# PR5009.net
KiCad netlist of a schematic drawn in EAGLE
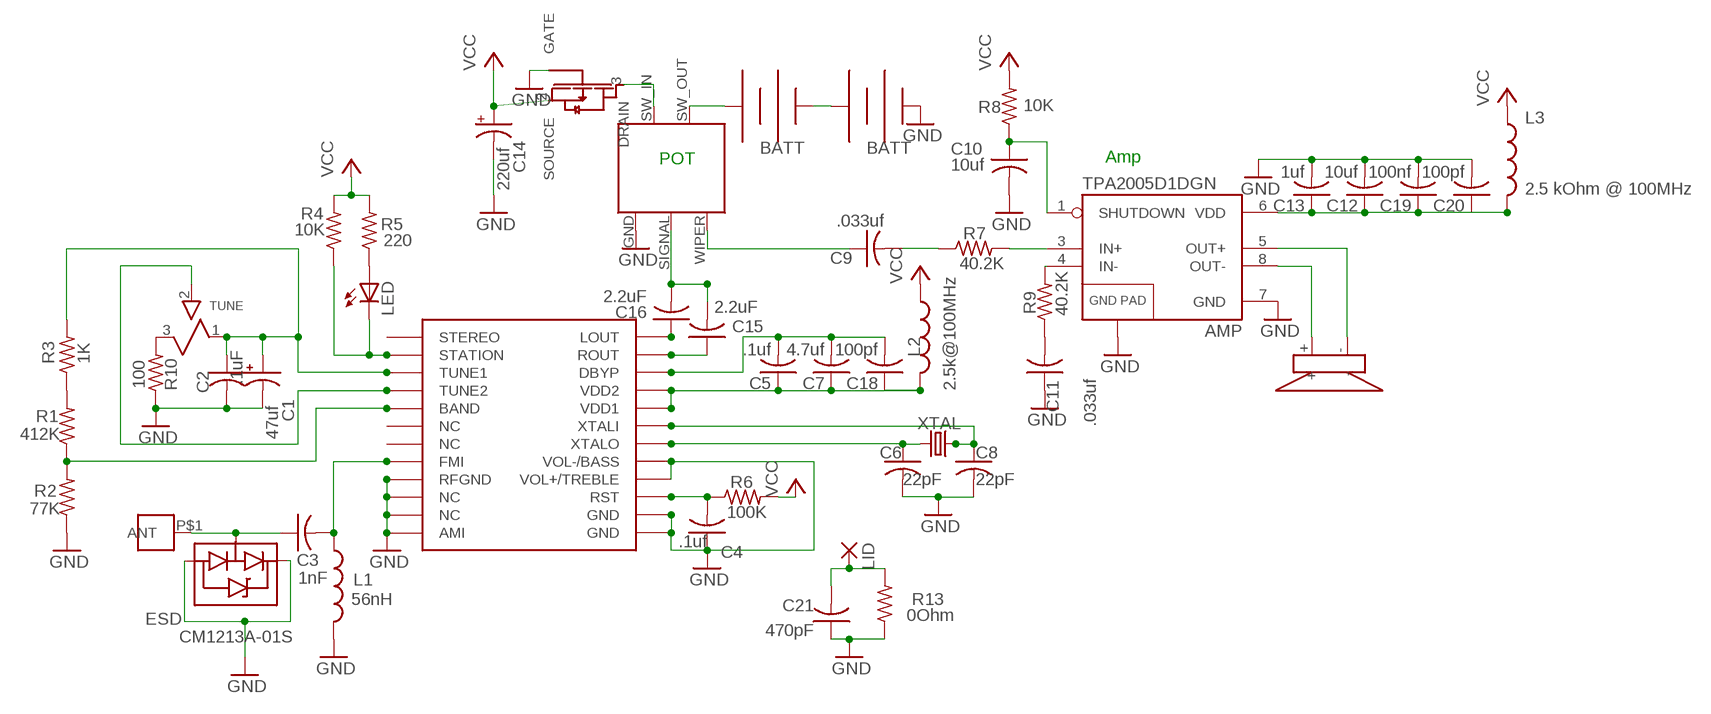
[diagram p0: schematic, sheet 1]

(export (version "E")
  (design (tool "Eeschema 10.0.6"))
  (components
    (comp (ref "AMP")
      (value "TPA2005D1DGN")
      (footprint "eagle-import:POWER-SOP8")
      (libsource (lib "eagle-import") (part "TPA2005D1DGN"))
    )
    (comp (ref "ANT")
      (value "M3_SCREW_POST")
      (footprint "eagle-import:M3_SCREW_POST")
      (libsource (lib "eagle-import") (part "M3_SCREW_POST"))
    )
    (comp (ref "C1")
      (value "47uf")
      (footprint "eagle-import:E2-5")
      (libsource (lib "eagle-import") (part "CPOL-USE2-5"))
    )
    (comp (ref "C2")
      (value ".1uF")
      (footprint "eagle-import:C0603")
      (libsource (lib "eagle-import") (part "C-USC0603"))
    )
    (comp (ref "C3")
      (value "1nF")
      (footprint "eagle-import:C0603")
      (libsource (lib "eagle-import") (part "C-USC0603"))
    )
    (comp (ref "C4")
      (value ".1uf")
      (footprint "eagle-import:C0603")
      (libsource (lib "eagle-import") (part "C-USC0603"))
    )
    (comp (ref "C5")
      (value ".1uf")
      (footprint "eagle-import:C0603")
      (libsource (lib "eagle-import") (part "C-USC0603"))
    )
    (comp (ref "C6")
      (value "22pF")
      (footprint "eagle-import:C0603")
      (libsource (lib "eagle-import") (part "C-USC0603"))
    )
    (comp (ref "C7")
      (value "4.7uf")
      (footprint "eagle-import:C0603")
      (libsource (lib "eagle-import") (part "C-USC0603"))
    )
    (comp (ref "C8")
      (value "22pF")
      (footprint "eagle-import:C0603")
      (libsource (lib "eagle-import") (part "C-USC0603"))
    )
    (comp (ref "C9")
      (value ".033uf")
      (footprint "eagle-import:C0603")
      (libsource (lib "eagle-import") (part "C-USC0603"))
    )
    (comp (ref "C10")
      (value "10uf")
      (footprint "eagle-import:C0603")
      (libsource (lib "eagle-import") (part "C-USC0603"))
    )
    (comp (ref "C11")
      (value ".033uf")
      (footprint "eagle-import:C0603")
      (libsource (lib "eagle-import") (part "C-USC0603"))
    )
    (comp (ref "C12")
      (value "10uf")
      (footprint "eagle-import:C0603")
      (libsource (lib "eagle-import") (part "C-USC0603"))
    )
    (comp (ref "C13")
      (value "1uf")
      (footprint "eagle-import:C0603")
      (libsource (lib "eagle-import") (part "C-USC0603"))
    )
    (comp (ref "C14")
      (value "220uf")
      (footprint "eagle-import:E2-5")
      (libsource (lib "eagle-import") (part "CPOL-USE2-5"))
    )
    (comp (ref "C15")
      (value "2.2uF")
      (footprint "eagle-import:C0603")
      (libsource (lib "eagle-import") (part "C-USC0603"))
    )
    (comp (ref "C16")
      (value "2.2uF")
      (footprint "eagle-import:C0603")
      (libsource (lib "eagle-import") (part "C-USC0603"))
    )
    (comp (ref "C18")
      (value "100pf")
      (footprint "eagle-import:C0603")
      (libsource (lib "eagle-import") (part "C-USC0603"))
    )
    (comp (ref "C19")
      (value "100nf")
      (footprint "eagle-import:C0603")
      (libsource (lib "eagle-import") (part "C-USC0603"))
    )
    (comp (ref "C20")
      (value "100pf")
      (footprint "eagle-import:C0603")
      (libsource (lib "eagle-import") (part "C-USC0603"))
    )
    (comp (ref "C21")
      (value "470pF")
      (footprint "eagle-import:C0603")
      (libsource (lib "eagle-import") (part "C-USC0603"))
    )
    (comp (ref "ESD")
      (value "CM1213A-01S")
      (footprint "eagle-import:SOT23-3")
      (libsource (lib "eagle-import") (part "CM1213A-01S"))
    )
    (comp (ref "FET")
      (value "SI2333DDS")
      (footprint "eagle-import:SI2333DDS")
      (libsource (lib "eagle-import") (part "SI2333DDS"))
    )
    (comp (ref "L1")
      (value "56nH")
      (footprint "eagle-import:0603")
      (libsource (lib "eagle-import") (part "INDUCTOR0603"))
    )
    (comp (ref "L2")
      (value "2.5k@100MHz")
      (footprint "eagle-import:0603")
      (libsource (lib "eagle-import") (part "INDUCTOR0603"))
    )
    (comp (ref "L3")
      (value "2.5 kOhm @ 100MHz")
      (footprint "eagle-import:0603")
      (libsource (lib "eagle-import") (part "INDUCTOR0603"))
    )
    (comp (ref "LED")
      (value "LEDCHIPLED_0805")
      (footprint "eagle-import:CHIPLED_0805")
      (libsource (lib "eagle-import") (part "LEDCHIPLED_0805"))
    )
    (comp (ref "LID")
      (value "2,54/1,0")
      (footprint "eagle-import:2,54_1,0")
      (libsource (lib "eagle-import") (part "2,54/1,0"))
    )
    (comp (ref "R1")
      (value "412K")
      (footprint "eagle-import:R0603")
      (libsource (lib "eagle-import") (part "R-US_R0603"))
    )
    (comp (ref "R2")
      (value "77K")
      (footprint "eagle-import:R0603")
      (libsource (lib "eagle-import") (part "R-US_R0603"))
    )
    (comp (ref "R3")
      (value "1K")
      (footprint "eagle-import:R0603")
      (libsource (lib "eagle-import") (part "R-US_R0603"))
    )
    (comp (ref "R4")
      (value "10K")
      (footprint "eagle-import:R0603")
      (libsource (lib "eagle-import") (part "R-US_R0603"))
    )
    (comp (ref "R5")
      (value "220")
      (footprint "eagle-import:R0603")
      (libsource (lib "eagle-import") (part "R-US_R0603"))
    )
    (comp (ref "R6")
      (value "100K")
      (footprint "eagle-import:R0603")
      (libsource (lib "eagle-import") (part "R-US_R0603"))
    )
    (comp (ref "R7")
      (value "40.2K")
      (footprint "eagle-import:R0603")
      (libsource (lib "eagle-import") (part "R-US_R0603"))
    )
    (comp (ref "R8")
      (value "10K")
      (footprint "eagle-import:R0603")
      (libsource (lib "eagle-import") (part "R-US_R0603"))
    )
    (comp (ref "R9")
      (value "40.2K")
      (footprint "eagle-import:R0603")
      (libsource (lib "eagle-import") (part "R-US_R0603"))
    )
    (comp (ref "R10")
      (value "100")
      (footprint "eagle-import:R0603")
      (libsource (lib "eagle-import") (part "R-US_R0603"))
    )
    (comp (ref "R13")
      (value "0Ohm")
      (footprint "eagle-import:R0603")
      (libsource (lib "eagle-import") (part "R-US_R0603"))
    )
    (comp (ref "TUNE")
      (value "10k")
      (footprint "eagle-import:64XR_BOURNS_TRIMPOT")
      (libsource (lib "eagle-import") (part "64XR_BOURNS_TRIMPOT"))
    )
    (comp (ref "U$1")
      (value "BK-92_MPD_AA_BATT_CLIP")
      (footprint "eagle-import:BK-92_MPD_AA_BATT_CLIP")
      (libsource (lib "eagle-import") (part "BK-92_MPD_AA_BATT_CLIP"))
    )
    (comp (ref "U$2")
      (value "BK-92_MPD_AA_BATT_CLIP")
      (footprint "eagle-import:BK-92_MPD_AA_BATT_CLIP")
      (libsource (lib "eagle-import") (part "BK-92_MPD_AA_BATT_CLIP"))
    )
    (comp (ref "U$3")
      (value "CE32A_DAYTON_SPKR")
      (footprint "eagle-import:CE32A_DAYTON_SPKR")
      (libsource (lib "eagle-import") (part "CE32A_DAYTON_SPKR"))
    )
    (comp (ref "U$4")
      (value "SI4831_FM_IC")
      (footprint "eagle-import:SI4831_FM_IC")
      (libsource (lib "eagle-import") (part "SI4831_FM_IC"))
    )
    (comp (ref "U$5")
      (value "RV170SF_TAIWANA_POT_SW")
      (footprint "eagle-import:RV170SF_TAIWANA_POT_SW")
      (libsource (lib "eagle-import") (part "RV170SF_TAIWANA_POT_SW"))
    )
    (comp (ref "XTAL")
      (value "CRYSTAL32-SMD")
      (footprint "eagle-import:CRYSTAL-32KHZ-SMD")
      (libsource (lib "eagle-import") (part "CRYSTAL32-SMD"))
    )
  )
  (nets
    (net (code "1") (name "GND") (class "Default")
      (node (ref "AMP") (pin "7") (pinfunction "GND_7") (pintype "power_in"))
      (node (ref "AMP") (pin "9") (pinfunction "GND_9") (pintype "power_in"))
      (node (ref "C1") (pin "-") (pinfunction "-_-") (pintype "passive"))
      (node (ref "C10") (pin "2") (pinfunction "2_2") (pintype "passive"))
      (node (ref "C11") (pin "1") (pinfunction "1_1") (pintype "passive"))
      (node (ref "C12") (pin "2") (pinfunction "2_2") (pintype "passive"))
      (node (ref "C13") (pin "2") (pinfunction "2_2") (pintype "passive"))
      (node (ref "C14") (pin "-") (pinfunction "-_-") (pintype "passive"))
      (node (ref "C19") (pin "2") (pinfunction "2_2") (pintype "passive"))
      (node (ref "C2") (pin "2") (pinfunction "2_2") (pintype "passive"))
      (node (ref "C20") (pin "2") (pinfunction "2_2") (pintype "passive"))
      (node (ref "C21") (pin "1") (pinfunction "1_1") (pintype "passive"))
      (node (ref "C4") (pin "1") (pinfunction "1_1") (pintype "passive"))
      (node (ref "C6") (pin "2") (pinfunction "2_2") (pintype "passive"))
      (node (ref "C8") (pin "2") (pinfunction "2_2") (pintype "passive"))
      (node (ref "ESD") (pin "2") (pinfunction "VP_2") (pintype "passive"))
      (node (ref "ESD") (pin "3") (pinfunction "VN_3") (pintype "passive"))
      (node (ref "FET") (pin "1") (pinfunction "GATE_1") (pintype "bidirectional"))
      (node (ref "L1") (pin "2") (pinfunction "2_2") (pintype "passive"))
      (node (ref "R10") (pin "1") (pinfunction "1_1") (pintype "passive"))
      (node (ref "R13") (pin "1") (pinfunction "1_1") (pintype "passive"))
      (node (ref "R2") (pin "1") (pinfunction "1_1") (pintype "passive"))
      (node (ref "U$2") (pin "NEG") (pinfunction "NEG_NEG") (pintype "bidirectional"))
      (node (ref "U$2") (pin "NEG@2") (pinfunction "NEG_NEG@2") (pintype "bidirectional"))
      (node (ref "U$4") (pin "AMI") (pinfunction "AMI_AMI") (pintype "bidirectional"))
      (node (ref "U$4") (pin "GND") (pinfunction "GND_GND") (pintype "bidirectional"))
      (node (ref "U$4") (pin "GND@2") (pinfunction "GND_GND@2") (pintype "bidirectional"))
      (node (ref "U$4") (pin "NC@3") (pinfunction "NC_NC@3") (pintype "bidirectional"))
      (node (ref "U$4") (pin "NC@4") (pinfunction "NC_NC@4") (pintype "bidirectional"))
      (node (ref "U$4") (pin "RFGND") (pinfunction "RFGND_RFGND") (pintype "bidirectional"))
      (node (ref "U$4") (pin "VOL+/TREBLE") (pinfunction "VOL+/TREBLE_VOL+/TREBLE") (pintype "bidirectional"))
      (node (ref "U$4") (pin "VOL-/BASS") (pinfunction "VOL-/BASS_VOL-/BASS") (pintype "bidirectional"))
      (node (ref "U$5") (pin "GND") (pinfunction "GND_GND") (pintype "bidirectional"))
    )
    (net (code "2") (name "Net-(AMP-IN+)") (class "Default")
      (node (ref "AMP") (pin "3") (pinfunction "IN+_3") (pintype "bidirectional"))
      (node (ref "R7") (pin "2") (pinfunction "2_2") (pintype "passive"))
    )
    (net (code "3") (name "Net-(AMP-IN-)") (class "Default")
      (node (ref "AMP") (pin "4") (pinfunction "IN-_4") (pintype "bidirectional"))
      (node (ref "R9") (pin "2") (pinfunction "2_2") (pintype "passive"))
    )
    (net (code "4") (name "Net-(AMP-OUT+)") (class "Default")
      (node (ref "AMP") (pin "5") (pinfunction "OUT+_5") (pintype "bidirectional"))
      (node (ref "U$3") (pin "-") (pinfunction "-_-") (pintype "bidirectional"))
    )
    (net (code "5") (name "Net-(AMP-OUT-)") (class "Default")
      (node (ref "AMP") (pin "8") (pinfunction "OUT-_8") (pintype "bidirectional"))
      (node (ref "U$3") (pin "+") (pinfunction "+_+") (pintype "bidirectional"))
    )
    (net (code "6") (name "Net-(AMP-SHUTDOWN)") (class "Default")
      (node (ref "AMP") (pin "1") (pinfunction "SHUTDOWN_1") (pintype "input"))
      (node (ref "C10") (pin "1") (pinfunction "1_1") (pintype "passive"))
      (node (ref "R8") (pin "1") (pinfunction "1_1") (pintype "passive"))
    )
    (net (code "7") (name "Net-(AMP-VDD)") (class "Default")
      (node (ref "AMP") (pin "6") (pinfunction "VDD_6") (pintype "power_in"))
      (node (ref "C12") (pin "1") (pinfunction "1_1") (pintype "passive"))
      (node (ref "C13") (pin "1") (pinfunction "1_1") (pintype "passive"))
      (node (ref "C19") (pin "1") (pinfunction "1_1") (pintype "passive"))
      (node (ref "C20") (pin "1") (pinfunction "1_1") (pintype "passive"))
      (node (ref "L3") (pin "2") (pinfunction "2_2") (pintype "passive"))
    )
    (net (code "8") (name "Net-(ANT-ANT)") (class "Default")
      (node (ref "ANT") (pin "P$1") (pinfunction "ANT_P$1") (pintype "bidirectional"))
      (node (ref "C3") (pin "1") (pinfunction "1_1") (pintype "passive"))
      (node (ref "ESD") (pin "1") (pinfunction "CH_1") (pintype "passive"))
    )
    (net (code "9") (name "Net-(C1-Pad+)") (class "Default")
      (node (ref "C1") (pin "+") (pinfunction "+_+") (pintype "passive"))
      (node (ref "C2") (pin "1") (pinfunction "1_1") (pintype "passive"))
      (node (ref "R3") (pin "2") (pinfunction "2_2") (pintype "passive"))
      (node (ref "TUNE") (pin "1") (pinfunction "1_1") (pintype "bidirectional"))
      (node (ref "U$4") (pin "TUNE1") (pinfunction "TUNE1_TUNE1") (pintype "bidirectional"))
    )
    (net (code "10") (name "Net-(C3-Pad2)") (class "Default")
      (node (ref "C3") (pin "2") (pinfunction "2_2") (pintype "passive"))
      (node (ref "L1") (pin "1") (pinfunction "1_1") (pintype "passive"))
      (node (ref "U$4") (pin "FMI") (pinfunction "FMI_FMI") (pintype "bidirectional"))
    )
    (net (code "11") (name "Net-(C4-Pad2)") (class "Default")
      (node (ref "C4") (pin "2") (pinfunction "2_2") (pintype "passive"))
      (node (ref "R6") (pin "1") (pinfunction "1_1") (pintype "passive"))
      (node (ref "U$4") (pin "RST") (pinfunction "RST_RST") (pintype "bidirectional"))
    )
    (net (code "12") (name "Net-(C9-Pad1)") (class "Default")
      (node (ref "C9") (pin "1") (pinfunction "1_1") (pintype "passive"))
      (node (ref "U$5") (pin "WIPER") (pinfunction "WIPER_WIPER") (pintype "bidirectional"))
    )
    (net (code "13") (name "Net-(C9-Pad2)") (class "Default")
      (node (ref "C9") (pin "2") (pinfunction "2_2") (pintype "passive"))
      (node (ref "R7") (pin "1") (pinfunction "1_1") (pintype "passive"))
    )
    (net (code "14") (name "Net-(C11-Pad2)") (class "Default")
      (node (ref "C11") (pin "2") (pinfunction "2_2") (pintype "passive"))
      (node (ref "R9") (pin "1") (pinfunction "1_1") (pintype "passive"))
    )
    (net (code "15") (name "Net-(C15-Pad1)") (class "Default")
      (node (ref "C15") (pin "1") (pinfunction "1_1") (pintype "passive"))
      (node (ref "U$4") (pin "ROUT") (pinfunction "ROUT_ROUT") (pintype "bidirectional"))
    )
    (net (code "16") (name "Net-(C15-Pad2)") (class "Default")
      (node (ref "C15") (pin "2") (pinfunction "2_2") (pintype "passive"))
      (node (ref "C16") (pin "2") (pinfunction "2_2") (pintype "passive"))
      (node (ref "U$5") (pin "SIGNAL") (pinfunction "SIGNAL_SIGNAL") (pintype "bidirectional"))
    )
    (net (code "17") (name "Net-(C16-Pad1)") (class "Default")
      (node (ref "C16") (pin "1") (pinfunction "1_1") (pintype "passive"))
      (node (ref "U$4") (pin "LOUT") (pinfunction "LOUT_LOUT") (pintype "bidirectional"))
    )
    (net (code "18") (name "Net-(C18-Pad1)") (class "Default")
      (node (ref "C18") (pin "1") (pinfunction "1_1") (pintype "passive"))
      (node (ref "C5") (pin "1") (pinfunction "1_1") (pintype "passive"))
      (node (ref "C7") (pin "1") (pinfunction "1_1") (pintype "passive"))
      (node (ref "L2") (pin "2") (pinfunction "2_2") (pintype "passive"))
      (node (ref "U$4") (pin "VDD1") (pinfunction "VDD1_VDD1") (pintype "bidirectional"))
      (node (ref "U$4") (pin "VDD2") (pinfunction "VDD2_VDD2") (pintype "bidirectional"))
    )
    (net (code "19") (name "Net-(C18-Pad2)") (class "Default")
      (node (ref "C18") (pin "2") (pinfunction "2_2") (pintype "passive"))
      (node (ref "C5") (pin "2") (pinfunction "2_2") (pintype "passive"))
      (node (ref "C7") (pin "2") (pinfunction "2_2") (pintype "passive"))
      (node (ref "U$4") (pin "DBYP") (pinfunction "DBYP_DBYP") (pintype "bidirectional"))
    )
    (net (code "20") (name "Net-(FET-DRAIN)") (class "Default")
      (node (ref "FET") (pin "3") (pinfunction "DRAIN_3") (pintype "bidirectional"))
      (node (ref "U$5") (pin "SW_IN") (pinfunction "SW_IN_SW_IN") (pintype "bidirectional"))
    )
    (net (code "21") (name "Net-(LED-PadA)") (class "Default")
      (node (ref "LED") (pin "A") (pinfunction "A_A") (pintype "passive"))
      (node (ref "R5") (pin "1") (pinfunction "1_1") (pintype "passive"))
    )
    (net (code "22") (name "Net-(LED-PadC)") (class "Default")
      (node (ref "LED") (pin "C") (pinfunction "C_C") (pintype "passive"))
      (node (ref "R4") (pin "1") (pinfunction "1_1") (pintype "passive"))
      (node (ref "U$4") (pin "STATION") (pinfunction "STATION_STATION") (pintype "bidirectional"))
    )
    (net (code "23") (name "Net-(LID-P)") (class "Default")
      (node (ref "C21") (pin "2") (pinfunction "2_2") (pintype "passive"))
      (node (ref "LID") (pin "1") (pinfunction "P_1") (pintype "passive"))
      (node (ref "R13") (pin "2") (pinfunction "2_2") (pintype "passive"))
    )
    (net (code "24") (name "Net-(R1-Pad1)") (class "Default")
      (node (ref "R1") (pin "1") (pinfunction "1_1") (pintype "passive"))
      (node (ref "R2") (pin "2") (pinfunction "2_2") (pintype "passive"))
      (node (ref "U$4") (pin "BAND") (pinfunction "BAND_BAND") (pintype "bidirectional"))
    )
    (net (code "25") (name "Net-(R1-Pad2)") (class "Default")
      (node (ref "R1") (pin "2") (pinfunction "2_2") (pintype "passive"))
      (node (ref "R3") (pin "1") (pinfunction "1_1") (pintype "passive"))
    )
    (net (code "26") (name "Net-(R10-Pad2)") (class "Default")
      (node (ref "R10") (pin "2") (pinfunction "2_2") (pintype "passive"))
      (node (ref "TUNE") (pin "3") (pinfunction "3_3") (pintype "bidirectional"))
    )
    (net (code "27") (name "Net-(TUNE-Pad2)") (class "Default")
      (node (ref "TUNE") (pin "2") (pinfunction "2_2") (pintype "bidirectional"))
      (node (ref "U$4") (pin "TUNE2") (pinfunction "TUNE2_TUNE2") (pintype "bidirectional"))
    )
    (net (code "28") (name "Net-(U$1-NEG-PadNEG@2)") (class "Default")
      (node (ref "U$1") (pin "NEG") (pinfunction "NEG_NEG") (pintype "bidirectional"))
      (node (ref "U$1") (pin "NEG@2") (pinfunction "NEG_NEG@2") (pintype "bidirectional"))
      (node (ref "U$2") (pin "POS") (pinfunction "POS_POS") (pintype "bidirectional"))
      (node (ref "U$2") (pin "POS@2") (pinfunction "POS_POS@2") (pintype "bidirectional"))
    )
    (net (code "29") (name "Net-(U$1-POS-PadPOS@2)") (class "Default")
      (node (ref "U$1") (pin "POS") (pinfunction "POS_POS") (pintype "bidirectional"))
      (node (ref "U$1") (pin "POS@2") (pinfunction "POS_POS@2") (pintype "bidirectional"))
      (node (ref "U$5") (pin "SW_OUT") (pinfunction "SW_OUT_SW_OUT") (pintype "bidirectional"))
    )
    (net (code "30") (name "Net-(XTAL-1)") (class "Default")
      (node (ref "C8") (pin "1") (pinfunction "1_1") (pintype "passive"))
      (node (ref "U$4") (pin "XTALI") (pinfunction "XTALI_XTALI") (pintype "bidirectional"))
      (node (ref "XTAL") (pin "X1") (pinfunction "1_X1") (pintype "passive"))
    )
    (net (code "31") (name "Net-(XTAL-2)") (class "Default")
      (node (ref "C6") (pin "1") (pinfunction "1_1") (pintype "passive"))
      (node (ref "U$4") (pin "XTALO") (pinfunction "XTALO_XTALO") (pintype "bidirectional"))
      (node (ref "XTAL") (pin "X2") (pinfunction "2_X2") (pintype "passive"))
    )
    (net (code "32") (name "VCC") (class "Default")
      (node (ref "C14") (pin "+") (pinfunction "+_+") (pintype "passive"))
      (node (ref "FET") (pin "2") (pinfunction "SOURCE_2") (pintype "bidirectional"))
      (node (ref "L2") (pin "1") (pinfunction "1_1") (pintype "passive"))
      (node (ref "L3") (pin "1") (pinfunction "1_1") (pintype "passive"))
      (node (ref "R4") (pin "2") (pinfunction "2_2") (pintype "passive"))
      (node (ref "R5") (pin "2") (pinfunction "2_2") (pintype "passive"))
      (node (ref "R6") (pin "2") (pinfunction "2_2") (pintype "passive"))
      (node (ref "R8") (pin "2") (pinfunction "2_2") (pintype "passive"))
    )
    (net (code "33") (name "unconnected-(U$4-NC-PadNC@2)") (class "Default")
      (node (ref "U$4") (pin "NC@2") (pinfunction "NC_NC@2") (pintype "bidirectional"))
    )
    (net (code "34") (name "unconnected-(U$4-PadNC)") (class "Default")
      (node (ref "U$4") (pin "NC") (pinfunction "NC_NC") (pintype "bidirectional"))
    )
    (net (code "35") (name "unconnected-(U$4-PadSTEREO)") (class "Default")
      (node (ref "U$4") (pin "STEREO") (pinfunction "STEREO_STEREO") (pintype "bidirectional"))
    )
  )
)
